# MiniKeyb.net
KiCad netlist of a schematic drawn in EAGLE
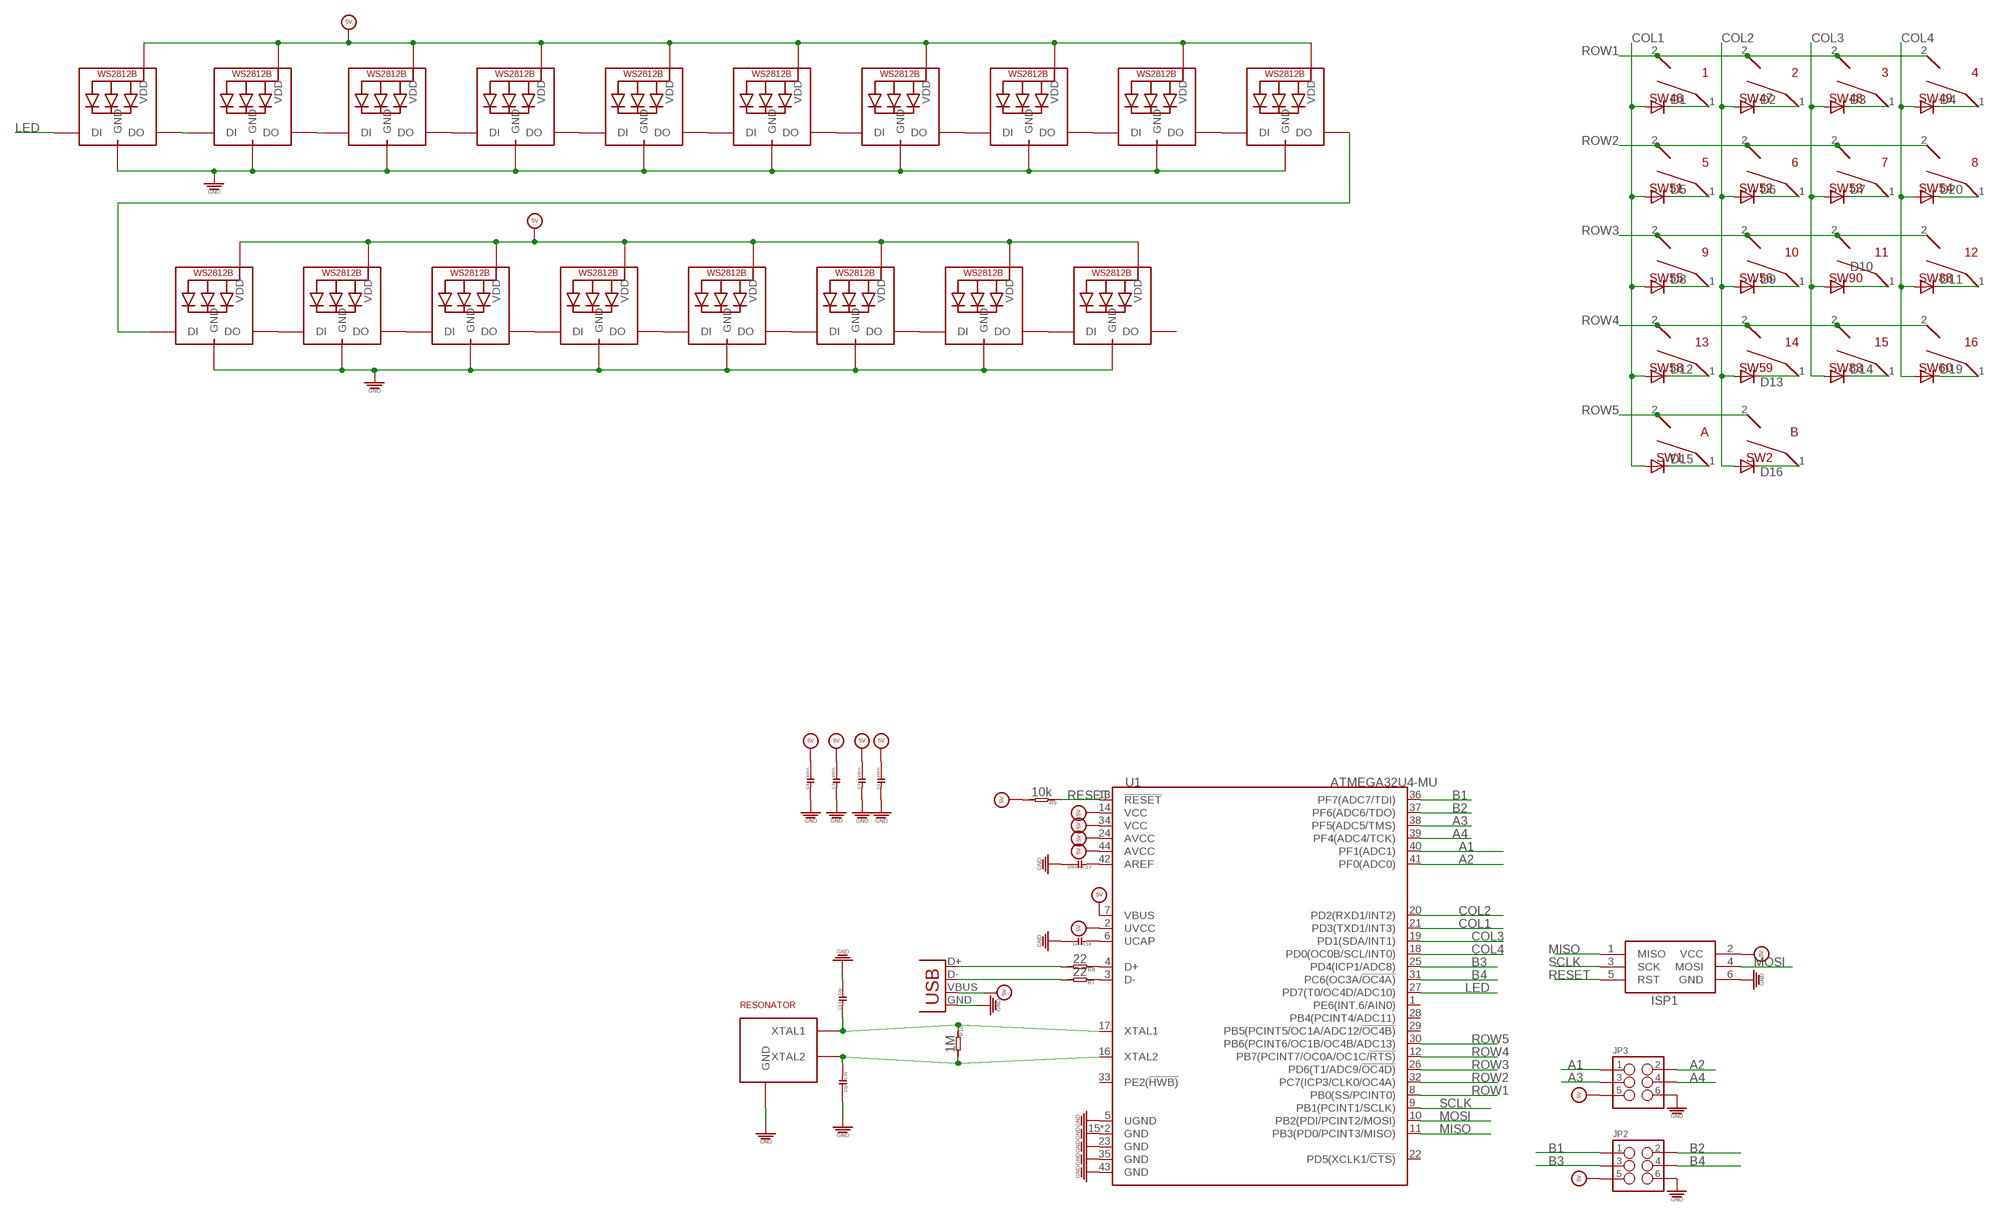
[diagram p0: schematic, sheet 1]

(export (version "E")
  (design (tool "Eeschema 10.0.6"))
  (components
    (comp (ref "C1")
      (value "100n")
      (footprint "eagle-import:C0603")
      (libsource (lib "eagle-import") (part "C-0603"))
    )
    (comp (ref "C2")
      (value "100n")
      (footprint "eagle-import:C0603")
      (libsource (lib "eagle-import") (part "C-0603"))
    )
    (comp (ref "C3")
      (value "100n")
      (footprint "eagle-import:C0603")
      (libsource (lib "eagle-import") (part "C-0603"))
    )
    (comp (ref "C4")
      (value "100n")
      (footprint "eagle-import:C0603")
      (libsource (lib "eagle-import") (part "C-0603"))
    )
    (comp (ref "C13")
      (value "100n")
      (footprint "eagle-import:C0603")
      (libsource (lib "eagle-import") (part "C-0603"))
    )
    (comp (ref "C14")
      (value "1u")
      (footprint "eagle-import:C0603")
      (libsource (lib "eagle-import") (part "C-0603"))
    )
    (comp (ref "C15")
      (value "22p")
      (footprint "eagle-import:C0603")
      (libsource (lib "eagle-import") (part "C-0603"))
    )
    (comp (ref "C16")
      (value "22p")
      (footprint "eagle-import:C0603")
      (libsource (lib "eagle-import") (part "C-0603"))
    )
    (comp (ref "D1")
      (value "CGRM4001-G")
      (footprint "eagle-import:SOD-123_MINI-SMA")
      (libsource (lib "eagle-import") (part "CGRM400-G1"))
    )
    (comp (ref "D2")
      (value "CGRM4001-G")
      (footprint "eagle-import:SOD-123_MINI-SMA")
      (libsource (lib "eagle-import") (part "CGRM400-G1"))
    )
    (comp (ref "D3")
      (value "CGRM4001-G")
      (footprint "eagle-import:SOD-123_MINI-SMA")
      (libsource (lib "eagle-import") (part "CGRM400-G1"))
    )
    (comp (ref "D4")
      (value "CGRM4001-G")
      (footprint "eagle-import:SOD-123_MINI-SMA")
      (libsource (lib "eagle-import") (part "CGRM400-G1"))
    )
    (comp (ref "D5")
      (value "CGRM4001-G")
      (footprint "eagle-import:SOD-123_MINI-SMA")
      (libsource (lib "eagle-import") (part "CGRM400-G1"))
    )
    (comp (ref "D6")
      (value "CGRM4001-G")
      (footprint "eagle-import:SOD-123_MINI-SMA")
      (libsource (lib "eagle-import") (part "CGRM400-G1"))
    )
    (comp (ref "D7")
      (value "CGRM4001-G")
      (footprint "eagle-import:SOD-123_MINI-SMA")
      (libsource (lib "eagle-import") (part "CGRM400-G1"))
    )
    (comp (ref "D8")
      (value "CGRM4001-G")
      (footprint "eagle-import:SOD-123_MINI-SMA")
      (libsource (lib "eagle-import") (part "CGRM400-G1"))
    )
    (comp (ref "D9")
      (value "CGRM4001-G")
      (footprint "eagle-import:SOD-123_MINI-SMA")
      (libsource (lib "eagle-import") (part "CGRM400-G1"))
    )
    (comp (ref "D10")
      (value "CGRM4001-G")
      (footprint "eagle-import:SOD-123_MINI-SMA")
      (libsource (lib "eagle-import") (part "CGRM400-G1"))
    )
    (comp (ref "D11")
      (value "CGRM4001-G")
      (footprint "eagle-import:SOD-123_MINI-SMA")
      (libsource (lib "eagle-import") (part "CGRM400-G1"))
    )
    (comp (ref "D12")
      (value "CGRM4001-G")
      (footprint "eagle-import:SOD-123_MINI-SMA")
      (libsource (lib "eagle-import") (part "CGRM400-G1"))
    )
    (comp (ref "D13")
      (value "CGRM4001-G")
      (footprint "eagle-import:SOD-123_MINI-SMA")
      (libsource (lib "eagle-import") (part "CGRM400-G1"))
    )
    (comp (ref "D14")
      (value "CGRM4001-G")
      (footprint "eagle-import:SOD-123_MINI-SMA")
      (libsource (lib "eagle-import") (part "CGRM400-G1"))
    )
    (comp (ref "D15")
      (value "CGRM4001-G")
      (footprint "eagle-import:SOD-123_MINI-SMA")
      (libsource (lib "eagle-import") (part "CGRM400-G1"))
    )
    (comp (ref "D16")
      (value "CGRM4001-G")
      (footprint "eagle-import:SOD-123_MINI-SMA")
      (libsource (lib "eagle-import") (part "CGRM400-G1"))
    )
    (comp (ref "D19")
      (value "CGRM4001-G")
      (footprint "eagle-import:SOD-123_MINI-SMA")
      (libsource (lib "eagle-import") (part "CGRM400-G1"))
    )
    (comp (ref "D20")
      (value "CGRM4001-G")
      (footprint "eagle-import:SOD-123_MINI-SMA")
      (libsource (lib "eagle-import") (part "CGRM400-G1"))
    )
    (comp (ref "ISP1")
      (value "AVRISP-6")
      (footprint "eagle-import:AVRISP")
      (libsource (lib "eagle-import") (part "AVRISP-6"))
    )
    (comp (ref "JP1")
      (value "USB-B")
      (footprint "eagle-import:USB-B-PTH")
      (libsource (lib "eagle-import") (part "USBPTH"))
    )
    (comp (ref "JP2")
      (value "M03X2")
      (footprint "eagle-import:2X3-SHROUDED")
      (libsource (lib "eagle-import") (part "M03X2"))
    )
    (comp (ref "JP3")
      (value "M03X2")
      (footprint "eagle-import:2X3-SHROUDED")
      (libsource (lib "eagle-import") (part "M03X2"))
    )
    (comp (ref "LED1")
      (value "WS2812B3535")
      (footprint "eagle-import:LED3535")
      (libsource (lib "eagle-import") (part "WS2812B3535"))
    )
    (comp (ref "LED2")
      (value "WS2812B3535")
      (footprint "eagle-import:LED3535")
      (libsource (lib "eagle-import") (part "WS2812B3535"))
    )
    (comp (ref "LED13")
      (value "WS2812B3535")
      (footprint "eagle-import:LED3535")
      (libsource (lib "eagle-import") (part "WS2812B3535"))
    )
    (comp (ref "LED14")
      (value "WS2812B3535")
      (footprint "eagle-import:LED3535")
      (libsource (lib "eagle-import") (part "WS2812B3535"))
    )
    (comp (ref "LED15")
      (value "WS2812B3535")
      (footprint "eagle-import:LED3535")
      (libsource (lib "eagle-import") (part "WS2812B3535"))
    )
    (comp (ref "LED16")
      (value "WS2812B3535")
      (footprint "eagle-import:LED3535")
      (libsource (lib "eagle-import") (part "WS2812B3535"))
    )
    (comp (ref "LED17")
      (value "WS2812B3535")
      (footprint "eagle-import:LED3535")
      (libsource (lib "eagle-import") (part "WS2812B3535"))
    )
    (comp (ref "LED18")
      (value "WS2812B3535")
      (footprint "eagle-import:LED3535")
      (libsource (lib "eagle-import") (part "WS2812B3535"))
    )
    (comp (ref "LED19")
      (value "WS2812B3535")
      (footprint "eagle-import:LED3535")
      (libsource (lib "eagle-import") (part "WS2812B3535"))
    )
    (comp (ref "LED20")
      (value "WS2812B3535")
      (footprint "eagle-import:LED3535")
      (libsource (lib "eagle-import") (part "WS2812B3535"))
    )
    (comp (ref "LED21")
      (value "WS2812B3535")
      (footprint "eagle-import:LED3535")
      (libsource (lib "eagle-import") (part "WS2812B3535"))
    )
    (comp (ref "LED22")
      (value "WS2812B3535")
      (footprint "eagle-import:LED3535")
      (libsource (lib "eagle-import") (part "WS2812B3535"))
    )
    (comp (ref "LED23")
      (value "WS2812B3535")
      (footprint "eagle-import:LED3535")
      (libsource (lib "eagle-import") (part "WS2812B3535"))
    )
    (comp (ref "LED24")
      (value "WS2812B3535")
      (footprint "eagle-import:LED3535")
      (libsource (lib "eagle-import") (part "WS2812B3535"))
    )
    (comp (ref "LED25")
      (value "WS2812B3535")
      (footprint "eagle-import:LED3535")
      (libsource (lib "eagle-import") (part "WS2812B3535"))
    )
    (comp (ref "LED26")
      (value "WS2812B3535")
      (footprint "eagle-import:LED3535")
      (libsource (lib "eagle-import") (part "WS2812B3535"))
    )
    (comp (ref "LED27")
      (value "WS2812B3535")
      (footprint "eagle-import:LED3535")
      (libsource (lib "eagle-import") (part "WS2812B3535"))
    )
    (comp (ref "LED28")
      (value "WS2812B3535")
      (footprint "eagle-import:LED3535")
      (libsource (lib "eagle-import") (part "WS2812B3535"))
    )
    (comp (ref "R7")
      (value "22")
      (footprint "eagle-import:R0603")
      (libsource (lib "eagle-import") (part "R-0603"))
    )
    (comp (ref "R8")
      (value "22")
      (footprint "eagle-import:R0603")
      (libsource (lib "eagle-import") (part "R-0603"))
    )
    (comp (ref "R9")
      (value "10k")
      (footprint "eagle-import:R0603")
      (libsource (lib "eagle-import") (part "R-0603"))
    )
    (comp (ref "R10")
      (value "1M")
      (footprint "eagle-import:R0603")
      (libsource (lib "eagle-import") (part "R-0603"))
    )
    (comp (ref "SW1")
      (value "A")
      (footprint "eagle-import:MX1A-XXNW")
      (libsource (lib "eagle-import") (part "CHERRY_MX_WITH_FIXING_PINS"))
    )
    (comp (ref "SW2")
      (value "B")
      (footprint "eagle-import:MX1A-XXNW")
      (libsource (lib "eagle-import") (part "CHERRY_MX_WITH_FIXING_PINS"))
    )
    (comp (ref "SW46")
      (value "1")
      (footprint "eagle-import:MX1A-XXNW")
      (libsource (lib "eagle-import") (part "CHERRY_MX_WITH_FIXING_PINS"))
    )
    (comp (ref "SW47")
      (value "2")
      (footprint "eagle-import:MX1A-XXNW")
      (libsource (lib "eagle-import") (part "CHERRY_MX_WITH_FIXING_PINS"))
    )
    (comp (ref "SW48")
      (value "3")
      (footprint "eagle-import:MX1A-XXNW")
      (libsource (lib "eagle-import") (part "CHERRY_MX_WITH_FIXING_PINS"))
    )
    (comp (ref "SW49")
      (value "4")
      (footprint "eagle-import:MX1A-XXNW")
      (libsource (lib "eagle-import") (part "CHERRY_MX_WITH_FIXING_PINS"))
    )
    (comp (ref "SW51")
      (value "5")
      (footprint "eagle-import:MX1A-XXNW")
      (libsource (lib "eagle-import") (part "CHERRY_MX_WITH_FIXING_PINS"))
    )
    (comp (ref "SW52")
      (value "6")
      (footprint "eagle-import:MX1A-XXNW")
      (libsource (lib "eagle-import") (part "CHERRY_MX_WITH_FIXING_PINS"))
    )
    (comp (ref "SW53")
      (value "7")
      (footprint "eagle-import:MX1A-XXNW")
      (libsource (lib "eagle-import") (part "CHERRY_MX_WITH_FIXING_PINS"))
    )
    (comp (ref "SW54")
      (value "8")
      (footprint "eagle-import:MX1A-XXNW")
      (libsource (lib "eagle-import") (part "CHERRY_MX_WITH_FIXING_PINS"))
    )
    (comp (ref "SW55")
      (value "9")
      (footprint "eagle-import:MX1A-XXNW")
      (libsource (lib "eagle-import") (part "CHERRY_MX_WITH_FIXING_PINS"))
    )
    (comp (ref "SW56")
      (value "10")
      (footprint "eagle-import:MX1A-XXNW")
      (libsource (lib "eagle-import") (part "CHERRY_MX_WITH_FIXING_PINS"))
    )
    (comp (ref "SW58")
      (value "13")
      (footprint "eagle-import:MX1A-XXNW")
      (libsource (lib "eagle-import") (part "CHERRY_MX_WITH_FIXING_PINS"))
    )
    (comp (ref "SW59")
      (value "14")
      (footprint "eagle-import:MX1A-XXNW")
      (libsource (lib "eagle-import") (part "CHERRY_MX_WITH_FIXING_PINS"))
    )
    (comp (ref "SW60")
      (value "16")
      (footprint "eagle-import:MX1A-XXNW")
      (libsource (lib "eagle-import") (part "CHERRY_MX_WITH_FIXING_PINS"))
    )
    (comp (ref "SW83")
      (value "15")
      (footprint "eagle-import:MX1A-XXNW")
      (libsource (lib "eagle-import") (part "CHERRY_MX_WITH_FIXING_PINS"))
    )
    (comp (ref "SW88")
      (value "12")
      (footprint "eagle-import:MX1A-XXNW")
      (libsource (lib "eagle-import") (part "CHERRY_MX_WITH_FIXING_PINS"))
    )
    (comp (ref "SW90")
      (value "11")
      (footprint "eagle-import:MX1A-XXNW")
      (libsource (lib "eagle-import") (part "CHERRY_MX_WITH_FIXING_PINS"))
    )
    (comp (ref "U$60")
      (value "RESONATOR")
      (footprint "eagle-import:16MHZXTAL")
      (libsource (lib "eagle-import") (part "RESONATOR"))
    )
    (comp (ref "U1")
      (value "ATMEGA32U4-MU")
      (footprint "eagle-import:QFN44")
      (libsource (lib "eagle-import") (part "ATMEGA32U4-MU"))
    )
  )
  (nets
    (net (code "1") (name "/A1") (class "Default")
      (node (ref "JP3") (pin "1") (pinfunction "1_1") (pintype "bidirectional"))
      (node (ref "U1") (pin "40") (pinfunction "PF1(ADC1)_40") (pintype "bidirectional"))
    )
    (net (code "2") (name "/A2") (class "Default")
      (node (ref "JP3") (pin "2") (pinfunction "2_2") (pintype "bidirectional"))
      (node (ref "U1") (pin "41") (pinfunction "PF0(ADC0)_41") (pintype "bidirectional"))
    )
    (net (code "3") (name "/A3") (class "Default")
      (node (ref "JP3") (pin "3") (pinfunction "3_3") (pintype "bidirectional"))
      (node (ref "U1") (pin "38") (pinfunction "PF5(ADC5/TMS)_38") (pintype "bidirectional"))
    )
    (net (code "4") (name "/A4") (class "Default")
      (node (ref "JP3") (pin "4") (pinfunction "4_4") (pintype "bidirectional"))
      (node (ref "U1") (pin "39") (pinfunction "PF4(ADC4/TCK)_39") (pintype "bidirectional"))
    )
    (net (code "5") (name "/B1") (class "Default")
      (node (ref "JP2") (pin "1") (pinfunction "1_1") (pintype "bidirectional"))
      (node (ref "U1") (pin "36") (pinfunction "PF7(ADC7/TDI)_36") (pintype "bidirectional"))
    )
    (net (code "6") (name "/B2") (class "Default")
      (node (ref "JP2") (pin "2") (pinfunction "2_2") (pintype "bidirectional"))
      (node (ref "U1") (pin "37") (pinfunction "PF6(ADC6/TDO)_37") (pintype "bidirectional"))
    )
    (net (code "7") (name "/B3") (class "Default")
      (node (ref "JP2") (pin "3") (pinfunction "3_3") (pintype "bidirectional"))
      (node (ref "U1") (pin "25") (pinfunction "PD4(ICP1/ADC8)_25") (pintype "bidirectional"))
    )
    (net (code "8") (name "/B4") (class "Default")
      (node (ref "JP2") (pin "4") (pinfunction "4_4") (pintype "bidirectional"))
      (node (ref "U1") (pin "31") (pinfunction "PC6(OC3A/~{OC4A})_31") (pintype "bidirectional"))
    )
    (net (code "9") (name "/COL1") (class "Default")
      (node (ref "D1") (pin "A") (pinfunction "A_A") (pintype "passive"))
      (node (ref "D12") (pin "A") (pinfunction "A_A") (pintype "passive"))
      (node (ref "D15") (pin "A") (pinfunction "A_A") (pintype "passive"))
      (node (ref "D5") (pin "A") (pinfunction "A_A") (pintype "passive"))
      (node (ref "D8") (pin "A") (pinfunction "A_A") (pintype "passive"))
      (node (ref "U1") (pin "21") (pinfunction "PD3(TXD1/INT3)_21") (pintype "bidirectional"))
    )
    (net (code "10") (name "/COL2") (class "Default")
      (node (ref "D13") (pin "A") (pinfunction "A_A") (pintype "passive"))
      (node (ref "D16") (pin "A") (pinfunction "A_A") (pintype "passive"))
      (node (ref "D2") (pin "A") (pinfunction "A_A") (pintype "passive"))
      (node (ref "D6") (pin "A") (pinfunction "A_A") (pintype "passive"))
      (node (ref "D9") (pin "A") (pinfunction "A_A") (pintype "passive"))
      (node (ref "U1") (pin "20") (pinfunction "PD2(RXD1/INT2)_20") (pintype "bidirectional"))
    )
    (net (code "11") (name "/COL3") (class "Default")
      (node (ref "D10") (pin "A") (pinfunction "A_A") (pintype "passive"))
      (node (ref "D14") (pin "A") (pinfunction "A_A") (pintype "passive"))
      (node (ref "D3") (pin "A") (pinfunction "A_A") (pintype "passive"))
      (node (ref "D7") (pin "A") (pinfunction "A_A") (pintype "passive"))
      (node (ref "U1") (pin "19") (pinfunction "PD1(SDA/INT1)_19") (pintype "bidirectional"))
    )
    (net (code "12") (name "/COL4") (class "Default")
      (node (ref "D11") (pin "A") (pinfunction "A_A") (pintype "passive"))
      (node (ref "D19") (pin "A") (pinfunction "A_A") (pintype "passive"))
      (node (ref "D20") (pin "A") (pinfunction "A_A") (pintype "passive"))
      (node (ref "D4") (pin "A") (pinfunction "A_A") (pintype "passive"))
      (node (ref "U1") (pin "18") (pinfunction "PD0(OC0B/SCL/INT0)_18") (pintype "bidirectional"))
    )
    (net (code "13") (name "/LED") (class "Default")
      (node (ref "LED13") (pin "4") (pinfunction "DI_4") (pintype "input"))
      (node (ref "U1") (pin "27") (pinfunction "PD7(T0/OC4D/ADC10)_27") (pintype "bidirectional"))
    )
    (net (code "14") (name "/MISO") (class "Default")
      (node (ref "ISP1") (pin "1") (pinfunction "MISO_1") (pintype "input"))
      (node (ref "U1") (pin "11") (pinfunction "PB3(PD0/PCINT3/MISO)_11") (pintype "bidirectional"))
    )
    (net (code "15") (name "/MOSI") (class "Default")
      (node (ref "ISP1") (pin "4") (pinfunction "MOSI_4") (pintype "output"))
      (node (ref "U1") (pin "10") (pinfunction "PB2(PDI/PCINT2/MOSI)_10") (pintype "bidirectional"))
    )
    (net (code "16") (name "/RESET") (class "Default")
      (node (ref "ISP1") (pin "5") (pinfunction "RST_5") (pintype "output"))
      (node (ref "R9") (pin "1") (pinfunction "1_1") (pintype "bidirectional"))
      (node (ref "U1") (pin "13") (pinfunction "~{RESET}_13") (pintype "bidirectional"))
    )
    (net (code "17") (name "/ROW1") (class "Default")
      (node (ref "SW46") (pin "2") (pinfunction "2_2") (pintype "passive"))
      (node (ref "SW47") (pin "2") (pinfunction "2_2") (pintype "passive"))
      (node (ref "SW48") (pin "2") (pinfunction "2_2") (pintype "passive"))
      (node (ref "SW49") (pin "2") (pinfunction "2_2") (pintype "passive"))
      (node (ref "U1") (pin "8") (pinfunction "PB0(SS/PCINT0)_8") (pintype "bidirectional"))
    )
    (net (code "18") (name "/ROW2") (class "Default")
      (node (ref "SW51") (pin "2") (pinfunction "2_2") (pintype "passive"))
      (node (ref "SW52") (pin "2") (pinfunction "2_2") (pintype "passive"))
      (node (ref "SW53") (pin "2") (pinfunction "2_2") (pintype "passive"))
      (node (ref "SW54") (pin "2") (pinfunction "2_2") (pintype "passive"))
      (node (ref "U1") (pin "32") (pinfunction "PC7(ICP3/CLK0/OC4A)_32") (pintype "bidirectional"))
    )
    (net (code "19") (name "/ROW3") (class "Default")
      (node (ref "SW55") (pin "2") (pinfunction "2_2") (pintype "passive"))
      (node (ref "SW56") (pin "2") (pinfunction "2_2") (pintype "passive"))
      (node (ref "SW88") (pin "2") (pinfunction "2_2") (pintype "passive"))
      (node (ref "SW90") (pin "2") (pinfunction "2_2") (pintype "passive"))
      (node (ref "U1") (pin "26") (pinfunction "PD6(T1/ADC9/~{OC4D})_26") (pintype "bidirectional"))
    )
    (net (code "20") (name "/ROW4") (class "Default")
      (node (ref "SW58") (pin "2") (pinfunction "2_2") (pintype "passive"))
      (node (ref "SW59") (pin "2") (pinfunction "2_2") (pintype "passive"))
      (node (ref "SW60") (pin "2") (pinfunction "2_2") (pintype "passive"))
      (node (ref "SW83") (pin "2") (pinfunction "2_2") (pintype "passive"))
      (node (ref "U1") (pin "12") (pinfunction "PB7(PCINT7/OC0A/OC1C/~{RTS})_12") (pintype "bidirectional"))
    )
    (net (code "21") (name "/ROW5") (class "Default")
      (node (ref "SW1") (pin "2") (pinfunction "2_2") (pintype "passive"))
      (node (ref "SW2") (pin "2") (pinfunction "2_2") (pintype "passive"))
      (node (ref "U1") (pin "30") (pinfunction "PB6(PCINT6/OC1B/OC4B/ADC13)_30") (pintype "bidirectional"))
    )
    (net (code "22") (name "/SCLK") (class "Default")
      (node (ref "ISP1") (pin "3") (pinfunction "SCK_3") (pintype "output"))
      (node (ref "U1") (pin "9") (pinfunction "PB1(PCINT1/SCLK)_9") (pintype "bidirectional"))
    )
    (net (code "23") (name "5V") (class "Default")
      (node (ref "C1") (pin "2") (pinfunction "2_2") (pintype "bidirectional"))
      (node (ref "C2") (pin "2") (pinfunction "2_2") (pintype "bidirectional"))
      (node (ref "C3") (pin "2") (pinfunction "2_2") (pintype "bidirectional"))
      (node (ref "C4") (pin "2") (pinfunction "2_2") (pintype "bidirectional"))
      (node (ref "ISP1") (pin "2") (pinfunction "VCC_2") (pintype "power_in"))
      (node (ref "JP1") (pin "VBUS") (pinfunction "VBUS_VBUS") (pintype "bidirectional"))
      (node (ref "JP2") (pin "5") (pinfunction "5_5") (pintype "bidirectional"))
      (node (ref "JP3") (pin "5") (pinfunction "5_5") (pintype "bidirectional"))
      (node (ref "LED1") (pin "1") (pinfunction "VDD_1") (pintype "power_in"))
      (node (ref "LED13") (pin "1") (pinfunction "VDD_1") (pintype "power_in"))
      (node (ref "LED14") (pin "1") (pinfunction "VDD_1") (pintype "power_in"))
      (node (ref "LED15") (pin "1") (pinfunction "VDD_1") (pintype "power_in"))
      (node (ref "LED16") (pin "1") (pinfunction "VDD_1") (pintype "power_in"))
      (node (ref "LED17") (pin "1") (pinfunction "VDD_1") (pintype "power_in"))
      (node (ref "LED18") (pin "1") (pinfunction "VDD_1") (pintype "power_in"))
      (node (ref "LED19") (pin "1") (pinfunction "VDD_1") (pintype "power_in"))
      (node (ref "LED2") (pin "1") (pinfunction "VDD_1") (pintype "power_in"))
      (node (ref "LED20") (pin "1") (pinfunction "VDD_1") (pintype "power_in"))
      (node (ref "LED21") (pin "1") (pinfunction "VDD_1") (pintype "power_in"))
      (node (ref "LED22") (pin "1") (pinfunction "VDD_1") (pintype "power_in"))
      (node (ref "LED23") (pin "1") (pinfunction "VDD_1") (pintype "power_in"))
      (node (ref "LED24") (pin "1") (pinfunction "VDD_1") (pintype "power_in"))
      (node (ref "LED25") (pin "1") (pinfunction "VDD_1") (pintype "power_in"))
      (node (ref "LED26") (pin "1") (pinfunction "VDD_1") (pintype "power_in"))
      (node (ref "LED27") (pin "1") (pinfunction "VDD_1") (pintype "power_in"))
      (node (ref "LED28") (pin "1") (pinfunction "VDD_1") (pintype "power_in"))
      (node (ref "R9") (pin "2") (pinfunction "2_2") (pintype "bidirectional"))
      (node (ref "U1") (pin "14") (pinfunction "VCC_14") (pintype "bidirectional"))
      (node (ref "U1") (pin "2") (pinfunction "UVCC_2") (pintype "bidirectional"))
      (node (ref "U1") (pin "24") (pinfunction "AVCC_24") (pintype "bidirectional"))
      (node (ref "U1") (pin "34") (pinfunction "VCC_34") (pintype "bidirectional"))
      (node (ref "U1") (pin "44") (pinfunction "AVCC_44") (pintype "bidirectional"))
      (node (ref "U1") (pin "7") (pinfunction "VBUS_7") (pintype "bidirectional"))
    )
    (net (code "24") (name "GND") (class "Default")
      (node (ref "C1") (pin "1") (pinfunction "1_1") (pintype "bidirectional"))
      (node (ref "C13") (pin "2") (pinfunction "2_2") (pintype "bidirectional"))
      (node (ref "C14") (pin "2") (pinfunction "2_2") (pintype "bidirectional"))
      (node (ref "C15") (pin "2") (pinfunction "2_2") (pintype "bidirectional"))
      (node (ref "C16") (pin "2") (pinfunction "2_2") (pintype "bidirectional"))
      (node (ref "C2") (pin "1") (pinfunction "1_1") (pintype "bidirectional"))
      (node (ref "C3") (pin "1") (pinfunction "1_1") (pintype "bidirectional"))
      (node (ref "C4") (pin "1") (pinfunction "1_1") (pintype "bidirectional"))
      (node (ref "ISP1") (pin "6") (pinfunction "GND_6") (pintype "power_in"))
      (node (ref "JP1") (pin "GND") (pinfunction "GND_GND") (pintype "bidirectional"))
      (node (ref "JP2") (pin "6") (pinfunction "6_6") (pintype "bidirectional"))
      (node (ref "JP3") (pin "6") (pinfunction "6_6") (pintype "bidirectional"))
      (node (ref "LED1") (pin "3") (pinfunction "GND_3") (pintype "power_in"))
      (node (ref "LED13") (pin "3") (pinfunction "GND_3") (pintype "power_in"))
      (node (ref "LED14") (pin "3") (pinfunction "GND_3") (pintype "power_in"))
      (node (ref "LED15") (pin "3") (pinfunction "GND_3") (pintype "power_in"))
      (node (ref "LED16") (pin "3") (pinfunction "GND_3") (pintype "power_in"))
      (node (ref "LED17") (pin "3") (pinfunction "GND_3") (pintype "power_in"))
      (node (ref "LED18") (pin "3") (pinfunction "GND_3") (pintype "power_in"))
      (node (ref "LED19") (pin "3") (pinfunction "GND_3") (pintype "power_in"))
      (node (ref "LED2") (pin "3") (pinfunction "GND_3") (pintype "power_in"))
      (node (ref "LED20") (pin "3") (pinfunction "GND_3") (pintype "power_in"))
      (node (ref "LED21") (pin "3") (pinfunction "GND_3") (pintype "power_in"))
      (node (ref "LED22") (pin "3") (pinfunction "GND_3") (pintype "power_in"))
      (node (ref "LED23") (pin "3") (pinfunction "GND_3") (pintype "power_in"))
      (node (ref "LED24") (pin "3") (pinfunction "GND_3") (pintype "power_in"))
      (node (ref "LED25") (pin "3") (pinfunction "GND_3") (pintype "power_in"))
      (node (ref "LED26") (pin "3") (pinfunction "GND_3") (pintype "power_in"))
      (node (ref "LED27") (pin "3") (pinfunction "GND_3") (pintype "power_in"))
      (node (ref "LED28") (pin "3") (pinfunction "GND_3") (pintype "power_in"))
      (node (ref "U$60") (pin "P$2") (pinfunction "GND_P$2") (pintype "bidirectional"))
      (node (ref "U$60") (pin "P$4") (pinfunction "GND_P$4") (pintype "bidirectional"))
      (node (ref "U1") (pin "15") (pinfunction "GND_15") (pintype "bidirectional"))
      (node (ref "U1") (pin "23") (pinfunction "GND_23") (pintype "bidirectional"))
      (node (ref "U1") (pin "35") (pinfunction "GND_35") (pintype "bidirectional"))
      (node (ref "U1") (pin "43") (pinfunction "GND_43") (pintype "bidirectional"))
      (node (ref "U1") (pin "5") (pinfunction "UGND_5") (pintype "bidirectional"))
      (node (ref "U1") (pin "TAB") (pinfunction "GND_TAB") (pintype "bidirectional"))
    )
    (net (code "25") (name "Net-(D1-PadC)") (class "Default")
      (node (ref "D1") (pin "C") (pinfunction "C_C") (pintype "passive"))
      (node (ref "SW46") (pin "1") (pinfunction "1_1") (pintype "passive"))
    )
    (net (code "26") (name "Net-(D2-PadC)") (class "Default")
      (node (ref "D2") (pin "C") (pinfunction "C_C") (pintype "passive"))
      (node (ref "SW47") (pin "1") (pinfunction "1_1") (pintype "passive"))
    )
    (net (code "27") (name "Net-(D3-PadC)") (class "Default")
      (node (ref "D3") (pin "C") (pinfunction "C_C") (pintype "passive"))
      (node (ref "SW48") (pin "1") (pinfunction "1_1") (pintype "passive"))
    )
    (net (code "28") (name "Net-(D4-PadC)") (class "Default")
      (node (ref "D4") (pin "C") (pinfunction "C_C") (pintype "passive"))
      (node (ref "SW49") (pin "1") (pinfunction "1_1") (pintype "passive"))
    )
    (net (code "29") (name "Net-(D5-PadC)") (class "Default")
      (node (ref "D5") (pin "C") (pinfunction "C_C") (pintype "passive"))
      (node (ref "SW51") (pin "1") (pinfunction "1_1") (pintype "passive"))
    )
    (net (code "30") (name "Net-(D6-PadC)") (class "Default")
      (node (ref "D6") (pin "C") (pinfunction "C_C") (pintype "passive"))
      (node (ref "SW52") (pin "1") (pinfunction "1_1") (pintype "passive"))
    )
    (net (code "31") (name "Net-(D7-PadC)") (class "Default")
      (node (ref "D7") (pin "C") (pinfunction "C_C") (pintype "passive"))
      (node (ref "SW53") (pin "1") (pinfunction "1_1") (pintype "passive"))
    )
    (net (code "32") (name "Net-(D8-PadC)") (class "Default")
      (node (ref "D8") (pin "C") (pinfunction "C_C") (pintype "passive"))
      (node (ref "SW55") (pin "1") (pinfunction "1_1") (pintype "passive"))
    )
    (net (code "33") (name "Net-(D9-PadC)") (class "Default")
      (node (ref "D9") (pin "C") (pinfunction "C_C") (pintype "passive"))
      (node (ref "SW56") (pin "1") (pinfunction "1_1") (pintype "passive"))
    )
    (net (code "34") (name "Net-(D10-PadC)") (class "Default")
      (node (ref "D10") (pin "C") (pinfunction "C_C") (pintype "passive"))
      (node (ref "SW90") (pin "1") (pinfunction "1_1") (pintype "passive"))
    )
    (net (code "35") (name "Net-(D11-PadC)") (class "Default")
      (node (ref "D11") (pin "C") (pinfunction "C_C") (pintype "passive"))
      (node (ref "SW88") (pin "1") (pinfunction "1_1") (pintype "passive"))
    )
    (net (code "36") (name "Net-(D12-PadC)") (class "Default")
      (node (ref "D12") (pin "C") (pinfunction "C_C") (pintype "passive"))
      (node (ref "SW58") (pin "1") (pinfunction "1_1") (pintype "passive"))
    )
    (net (code "37") (name "Net-(D13-PadC)") (class "Default")
      (node (ref "D13") (pin "C") (pinfunction "C_C") (pintype "passive"))
      (node (ref "SW59") (pin "1") (pinfunction "1_1") (pintype "passive"))
    )
    (net (code "38") (name "Net-(D14-PadC)") (class "Default")
      (node (ref "D14") (pin "C") (pinfunction "C_C") (pintype "passive"))
      (node (ref "SW83") (pin "1") (pinfunction "1_1") (pintype "passive"))
    )
    (net (code "39") (name "Net-(D15-PadC)") (class "Default")
      (node (ref "D15") (pin "C") (pinfunction "C_C") (pintype "passive"))
      (node (ref "SW1") (pin "1") (pinfunction "1_1") (pintype "passive"))
    )
    (net (code "40") (name "Net-(D16-PadC)") (class "Default")
      (node (ref "D16") (pin "C") (pinfunction "C_C") (pintype "passive"))
      (node (ref "SW2") (pin "1") (pinfunction "1_1") (pintype "passive"))
    )
    (net (code "41") (name "Net-(D19-PadC)") (class "Default")
      (node (ref "D19") (pin "C") (pinfunction "C_C") (pintype "passive"))
      (node (ref "SW60") (pin "1") (pinfunction "1_1") (pintype "passive"))
    )
    (net (code "42") (name "Net-(D20-PadC)") (class "Default")
      (node (ref "D20") (pin "C") (pinfunction "C_C") (pintype "passive"))
      (node (ref "SW54") (pin "1") (pinfunction "1_1") (pintype "passive"))
    )
    (net (code "43") (name "Net-(JP1-PadD+)") (class "Default")
      (node (ref "JP1") (pin "D+") (pinfunction "D+_D+") (pintype "bidirectional"))
      (node (ref "R8") (pin "2") (pinfunction "2_2") (pintype "bidirectional"))
    )
    (net (code "44") (name "Net-(JP1-PadD-)") (class "Default")
      (node (ref "JP1") (pin "D-") (pinfunction "D-_D-") (pintype "bidirectional"))
      (node (ref "R7") (pin "2") (pinfunction "2_2") (pintype "bidirectional"))
    )
    (net (code "45") (name "Net-(LED1-DI)") (class "Default")
      (node (ref "LED1") (pin "4") (pinfunction "DI_4") (pintype "input"))
      (node (ref "LED28") (pin "2") (pinfunction "DO_2") (pintype "output"))
    )
    (net (code "46") (name "Net-(LED1-DO)") (class "Default")
      (node (ref "LED1") (pin "2") (pinfunction "DO_2") (pintype "output"))
      (node (ref "LED2") (pin "4") (pinfunction "DI_4") (pintype "input"))
    )
    (net (code "47") (name "Net-(LED13-DO)") (class "Default")
      (node (ref "LED13") (pin "2") (pinfunction "DO_2") (pintype "output"))
      (node (ref "LED14") (pin "4") (pinfunction "DI_4") (pintype "input"))
    )
    (net (code "48") (name "Net-(LED14-DO)") (class "Default")
      (node (ref "LED14") (pin "2") (pinfunction "DO_2") (pintype "output"))
      (node (ref "LED15") (pin "4") (pinfunction "DI_4") (pintype "input"))
    )
    (net (code "49") (name "Net-(LED15-DO)") (class "Default")
      (node (ref "LED15") (pin "2") (pinfunction "DO_2") (pintype "output"))
      (node (ref "LED16") (pin "4") (pinfunction "DI_4") (pintype "input"))
    )
    (net (code "50") (name "Net-(LED16-DO)") (class "Default")
      (node (ref "LED16") (pin "2") (pinfunction "DO_2") (pintype "output"))
      (node (ref "LED17") (pin "4") (pinfunction "DI_4") (pintype "input"))
    )
    (net (code "51") (name "Net-(LED17-DO)") (class "Default")
      (node (ref "LED17") (pin "2") (pinfunction "DO_2") (pintype "output"))
      (node (ref "LED18") (pin "4") (pinfunction "DI_4") (pintype "input"))
    )
    (net (code "52") (name "Net-(LED18-DO)") (class "Default")
      (node (ref "LED18") (pin "2") (pinfunction "DO_2") (pintype "output"))
      (node (ref "LED19") (pin "4") (pinfunction "DI_4") (pintype "input"))
    )
    (net (code "53") (name "Net-(LED19-DO)") (class "Default")
      (node (ref "LED19") (pin "2") (pinfunction "DO_2") (pintype "output"))
      (node (ref "LED20") (pin "4") (pinfunction "DI_4") (pintype "input"))
    )
    (net (code "54") (name "Net-(LED20-DO)") (class "Default")
      (node (ref "LED20") (pin "2") (pinfunction "DO_2") (pintype "output"))
      (node (ref "LED21") (pin "4") (pinfunction "DI_4") (pintype "input"))
    )
    (net (code "55") (name "Net-(LED21-DO)") (class "Default")
      (node (ref "LED21") (pin "2") (pinfunction "DO_2") (pintype "output"))
      (node (ref "LED22") (pin "4") (pinfunction "DI_4") (pintype "input"))
    )
    (net (code "56") (name "Net-(LED22-DO)") (class "Default")
      (node (ref "LED22") (pin "2") (pinfunction "DO_2") (pintype "output"))
      (node (ref "LED23") (pin "4") (pinfunction "DI_4") (pintype "input"))
    )
    (net (code "57") (name "Net-(LED23-DO)") (class "Default")
      (node (ref "LED23") (pin "2") (pinfunction "DO_2") (pintype "output"))
      (node (ref "LED24") (pin "4") (pinfunction "DI_4") (pintype "input"))
    )
    (net (code "58") (name "Net-(LED24-DO)") (class "Default")
      (node (ref "LED24") (pin "2") (pinfunction "DO_2") (pintype "output"))
      (node (ref "LED25") (pin "4") (pinfunction "DI_4") (pintype "input"))
    )
    (net (code "59") (name "Net-(LED25-DO)") (class "Default")
      (node (ref "LED25") (pin "2") (pinfunction "DO_2") (pintype "output"))
      (node (ref "LED26") (pin "4") (pinfunction "DI_4") (pintype "input"))
    )
    (net (code "60") (name "Net-(LED26-DO)") (class "Default")
      (node (ref "LED26") (pin "2") (pinfunction "DO_2") (pintype "output"))
      (node (ref "LED27") (pin "4") (pinfunction "DI_4") (pintype "input"))
    )
    (net (code "61") (name "Net-(LED27-DO)") (class "Default")
      (node (ref "LED27") (pin "2") (pinfunction "DO_2") (pintype "output"))
      (node (ref "LED28") (pin "4") (pinfunction "DI_4") (pintype "input"))
    )
    (net (code "62") (name "Net-(U$60-XTAL1)") (class "Default")
      (node (ref "C15") (pin "1") (pinfunction "1_1") (pintype "bidirectional"))
      (node (ref "R10") (pin "1") (pinfunction "1_1") (pintype "bidirectional"))
      (node (ref "U$60") (pin "P$1") (pinfunction "XTAL1_P$1") (pintype "bidirectional"))
      (node (ref "U1") (pin "17") (pinfunction "XTAL1_17") (pintype "bidirectional"))
    )
    (net (code "63") (name "Net-(U$60-XTAL2)") (class "Default")
      (node (ref "C16") (pin "1") (pinfunction "1_1") (pintype "bidirectional"))
      (node (ref "R10") (pin "2") (pinfunction "2_2") (pintype "bidirectional"))
      (node (ref "U$60") (pin "P$3") (pinfunction "XTAL2_P$3") (pintype "bidirectional"))
      (node (ref "U1") (pin "16") (pinfunction "XTAL2_16") (pintype "bidirectional"))
    )
    (net (code "64") (name "Net-(U1-AREF)") (class "Default")
      (node (ref "C13") (pin "1") (pinfunction "1_1") (pintype "bidirectional"))
      (node (ref "U1") (pin "42") (pinfunction "AREF_42") (pintype "bidirectional"))
    )
    (net (code "65") (name "Net-(U1-D+)") (class "Default")
      (node (ref "R8") (pin "1") (pinfunction "1_1") (pintype "bidirectional"))
      (node (ref "U1") (pin "4") (pinfunction "D+_4") (pintype "bidirectional"))
    )
    (net (code "66") (name "Net-(U1-D-)") (class "Default")
      (node (ref "R7") (pin "1") (pinfunction "1_1") (pintype "bidirectional"))
      (node (ref "U1") (pin "3") (pinfunction "D-_3") (pintype "bidirectional"))
    )
    (net (code "67") (name "Net-(U1-UCAP)") (class "Default")
      (node (ref "C14") (pin "1") (pinfunction "1_1") (pintype "bidirectional"))
      (node (ref "U1") (pin "6") (pinfunction "UCAP_6") (pintype "bidirectional"))
    )
    (net (code "68") (name "unconnected-(LED2-DO-Pad2)") (class "Default")
      (node (ref "LED2") (pin "2") (pinfunction "DO_2") (pintype "output"))
    )
    (net (code "69") (name "unconnected-(U1-PB4(PCINT4{slash}ADC11)-Pad28)") (class "Default")
      (node (ref "U1") (pin "28") (pinfunction "PB4(PCINT4/ADC11)_28") (pintype "bidirectional"))
    )
    (net (code "70") (name "unconnected-(U1-PB5(PCINT5{slash}OC1A{slash}ADC12{slash}~{OC4B})-Pad29)") (class "Default")
      (node (ref "U1") (pin "29") (pinfunction "PB5(PCINT5/OC1A/ADC12/~{OC4B})_29") (pintype "bidirectional"))
    )
    (net (code "71") (name "unconnected-(U1-PD5(XCLK1{slash}~{CTS})-Pad22)") (class "Default")
      (node (ref "U1") (pin "22") (pinfunction "PD5(XCLK1/~{CTS})_22") (pintype "bidirectional"))
    )
    (net (code "72") (name "unconnected-(U1-PE2(~{HWB})-Pad33)") (class "Default")
      (node (ref "U1") (pin "33") (pinfunction "PE2(~{HWB})_33") (pintype "bidirectional"))
    )
    (net (code "73") (name "unconnected-(U1-PE6(INT.6{slash}AIN0)-Pad1)") (class "Default")
      (node (ref "U1") (pin "1") (pinfunction "PE6(INT.6/AIN0)_1") (pintype "bidirectional"))
    )
  )
)
